# Power_Control.net
KiCad netlist of a schematic drawn in Altium Designer
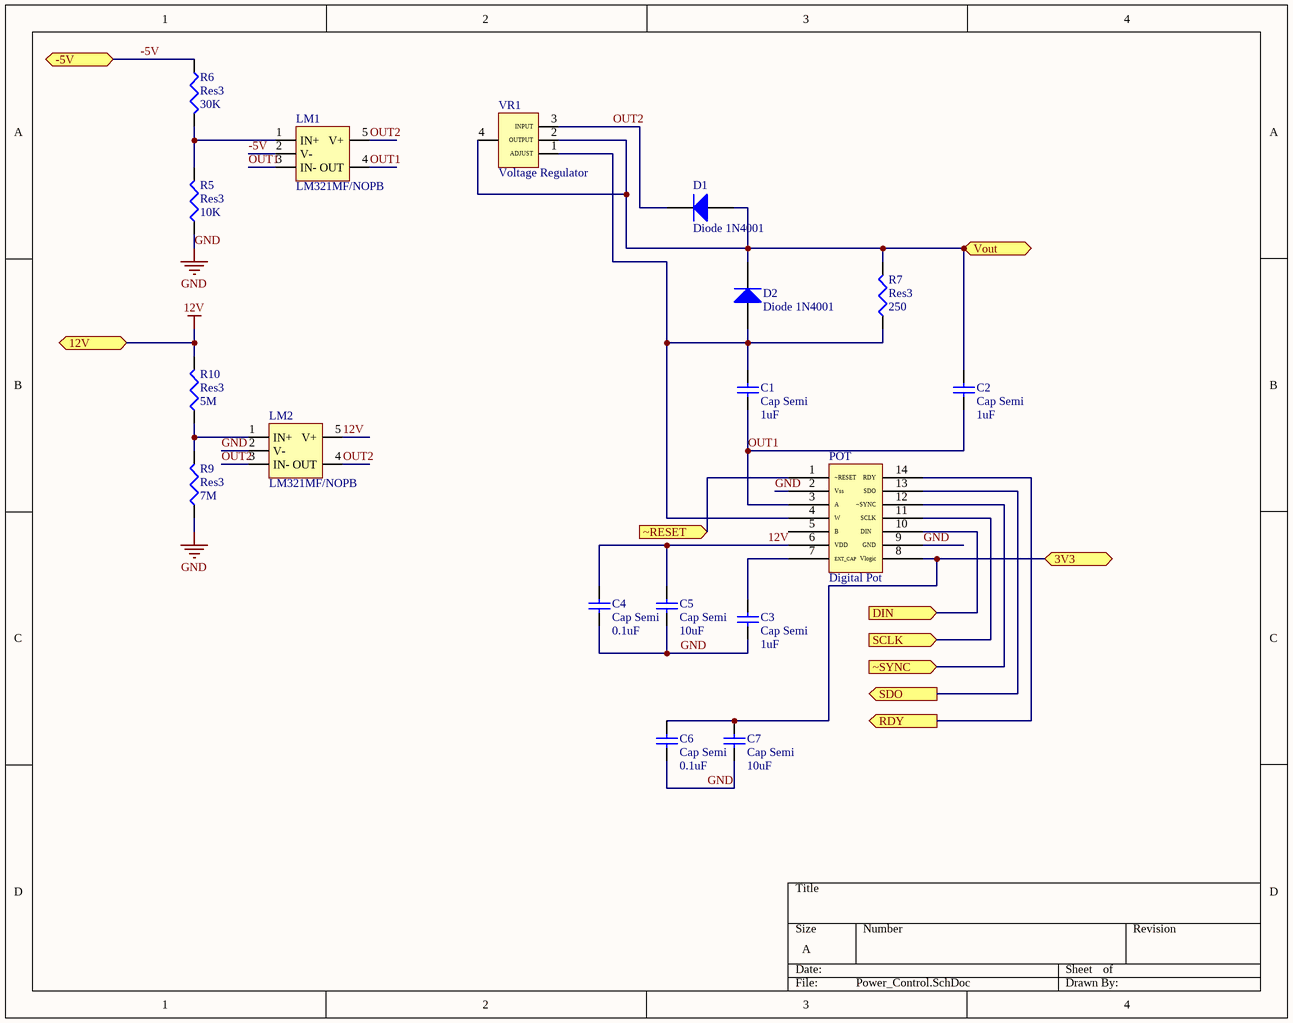
[diagram p0: Power_Control.SchDoc]

(export (version "E")
  (design (tool "Eeschema 10.0.6"))
  (components
    (comp (ref "C1")
      (value "Cap Semi")
      (footprint "C1206")
      (description "Capacitor (Semiconductor SIM Model)")
      (fields (field (name "ALTIUM_VALUE") "1uF") (field (name "PUBLISHER") "Altium Limited"))
      (libsource (lib "Miscellaneous Devices") (part "Cap Semi"))
    )
    (comp (ref "C2")
      (value "Cap Semi")
      (footprint "C1206")
      (description "Capacitor (Semiconductor SIM Model)")
      (fields (field (name "ALTIUM_VALUE") "1uF") (field (name "PUBLISHER") "Altium Limited"))
      (libsource (lib "Miscellaneous Devices") (part "Cap Semi"))
    )
    (comp (ref "C3")
      (value "Cap Semi")
      (footprint "C1206")
      (description "Capacitor (Semiconductor SIM Model)")
      (fields (field (name "ALTIUM_VALUE") "1uF") (field (name "PUBLISHER") "Altium Limited"))
      (libsource (lib "Miscellaneous Devices") (part "Cap Semi"))
    )
    (comp (ref "C4")
      (value "Cap Semi")
      (footprint "C1206")
      (description "Capacitor (Semiconductor SIM Model)")
      (fields (field (name "ALTIUM_VALUE") "0.1uF") (field (name "PUBLISHER") "Altium Limited"))
      (libsource (lib "Miscellaneous Devices") (part "Cap Semi"))
    )
    (comp (ref "C5")
      (value "Cap Semi")
      (footprint "C1206")
      (description "Capacitor (Semiconductor SIM Model)")
      (fields (field (name "ALTIUM_VALUE") "10uF") (field (name "PUBLISHER") "Altium Limited"))
      (libsource (lib "Miscellaneous Devices") (part "Cap Semi"))
    )
    (comp (ref "C6")
      (value "Cap Semi")
      (footprint "C1206")
      (description "Capacitor (Semiconductor SIM Model)")
      (fields (field (name "ALTIUM_VALUE") "0.1uF") (field (name "PUBLISHER") "Altium Limited"))
      (libsource (lib "Miscellaneous Devices") (part "Cap Semi"))
    )
    (comp (ref "C7")
      (value "Cap Semi")
      (footprint "C1206")
      (description "Capacitor (Semiconductor SIM Model)")
      (fields (field (name "ALTIUM_VALUE") "10uF") (field (name "PUBLISHER") "Altium Limited"))
      (libsource (lib "Miscellaneous Devices") (part "Cap Semi"))
    )
    (comp (ref "D1")
      (value "Diode 1N4001")
      (footprint "DO-41")
      (description "1 Amp General Purpose Rectifier")
      (fields (field (name "PUBLISHER") "Altium Limited"))
      (libsource (lib "Miscellaneous Devices") (part "Diode 1N4001"))
    )
    (comp (ref "D2")
      (value "Diode 1N4001")
      (footprint "DO-41")
      (description "1 Amp General Purpose Rectifier")
      (fields (field (name "PUBLISHER") "Altium Limited"))
      (libsource (lib "Miscellaneous Devices") (part "Diode 1N4001"))
    )
    (comp (ref "LM1")
      (value "LM321MF/NOPB")
      (description "IC OPAMP GP 1MHZ SOT23-5")
      (fields (field (name "MANUFACTURER") "Texas Instruments"))
      (libsource (lib "NORMS_LIB") (part "LM321MF/NOPB"))
    )
    (comp (ref "LM2")
      (value "LM321MF/NOPB")
      (description "IC OPAMP GP 1MHZ SOT23-5")
      (fields (field (name "MANUFACTURER") "Texas Instruments"))
      (libsource (lib "NORMS_LIB") (part "LM321MF/NOPB"))
    )
    (comp (ref "POT")
      (value "Digital Pot")
      (description "IC DGTL POT 1024POS 20K 14TSSOP")
      (fields
        (field (name "MANUFACTURER") "Analog Devices Inc.")
        (field (name "MANUFACTURER PART NUMBER") "AD5293BRUZ-20")
      )
      (libsource (lib "NORMS_LIB") (part "Digital Pot"))
    )
    (comp (ref "R5")
      (value "Res3")
      (footprint "J1-0603")
      (description "Resistor")
      (fields (field (name "ALTIUM_VALUE") "10K") (field (name "PUBLISHER") "Altium Limited"))
      (libsource (lib "Miscellaneous Devices") (part "Res3"))
    )
    (comp (ref "R6")
      (value "Res3")
      (footprint "J1-0603")
      (description "Resistor")
      (fields (field (name "ALTIUM_VALUE") "30K") (field (name "PUBLISHER") "Altium Limited"))
      (libsource (lib "Miscellaneous Devices") (part "Res3"))
    )
    (comp (ref "R7")
      (value "Res3")
      (footprint "J1-0603")
      (description "Resistor")
      (fields (field (name "ALTIUM_VALUE") "250") (field (name "PUBLISHER") "Altium Limited"))
      (libsource (lib "Miscellaneous Devices") (part "Res3"))
    )
    (comp (ref "R9")
      (value "Res3")
      (footprint "J1-0603")
      (description "Resistor")
      (fields (field (name "ALTIUM_VALUE") "7M") (field (name "PUBLISHER") "Altium Limited"))
      (libsource (lib "Miscellaneous Devices") (part "Res3"))
    )
    (comp (ref "R10")
      (value "Res3")
      (footprint "J1-0603")
      (description "Resistor")
      (fields (field (name "ALTIUM_VALUE") "5M") (field (name "PUBLISHER") "Altium Limited"))
      (libsource (lib "Miscellaneous Devices") (part "Res3"))
    )
    (comp (ref "VR1")
      (value "Voltage Regulator")
      (footprint "volt_reg")
      (description "IC REG LDO ADJ 1.5A DDPAK")
      (fields
        (field (name "MANUFACTURER") "Texas Instruments")
        (field (name "MANUFACTURER PART NUMBER") "LM317KTTR")
      )
      (libsource (lib "NORMS_LIB") (part "Voltage Regulator"))
    )
  )
  (nets
    (net (code "1") (name "/-5V") (class "Default")
      (node (ref "LM1") (pin "2") (pinfunction "V-_2") (pintype "passive"))
      (node (ref "R6") (pin "1") (pinfunction "1_1") (pintype "passive"))
    )
    (net (code "2") (name "/3V3") (class "Default")
      (node (ref "C6") (pin "2") (pinfunction "2_2") (pintype "passive"))
      (node (ref "C7") (pin "2") (pinfunction "2_2") (pintype "passive"))
      (node (ref "POT") (pin "8") (pinfunction "Vlogic_8") (pintype "passive"))
    )
    (net (code "3") (name "/DIN") (class "Default")
      (node (ref "POT") (pin "10") (pinfunction "DIN_10") (pintype "passive"))
    )
    (net (code "4") (name "/OUT1") (class "Default")
      (node (ref "C1") (pin "1") (pinfunction "1_1") (pintype "passive"))
      (node (ref "C2") (pin "1") (pinfunction "1_1") (pintype "passive"))
      (node (ref "LM1") (pin "3") (pinfunction "IN-_3") (pintype "passive"))
      (node (ref "LM1") (pin "4") (pinfunction "OUT_4") (pintype "passive"))
      (node (ref "POT") (pin "3") (pinfunction "A_3") (pintype "passive"))
    )
    (net (code "5") (name "/OUT2") (class "Default")
      (node (ref "D1") (pin "2") (pinfunction "K_2") (pintype "passive"))
      (node (ref "LM1") (pin "5") (pinfunction "V+_5") (pintype "passive"))
      (node (ref "LM2") (pin "3") (pinfunction "IN-_3") (pintype "passive"))
      (node (ref "LM2") (pin "4") (pinfunction "OUT_4") (pintype "passive"))
      (node (ref "VR1") (pin "3") (pinfunction "INPUT_3") (pintype "passive"))
    )
    (net (code "6") (name "/RDY") (class "Default")
      (node (ref "POT") (pin "14") (pinfunction "RDY_14") (pintype "passive"))
    )
    (net (code "7") (name "/SCLK") (class "Default")
      (node (ref "POT") (pin "11") (pinfunction "SCLK_11") (pintype "passive"))
    )
    (net (code "8") (name "/SDO") (class "Default")
      (node (ref "POT") (pin "13") (pinfunction "SDO_13") (pintype "passive"))
    )
    (net (code "9") (name "/Vout") (class "Default")
      (node (ref "C2") (pin "2") (pinfunction "2_2") (pintype "passive"))
      (node (ref "D1") (pin "1") (pinfunction "A_1") (pintype "passive"))
      (node (ref "D2") (pin "2") (pinfunction "K_2") (pintype "passive"))
      (node (ref "R7") (pin "2") (pinfunction "2_2") (pintype "passive"))
      (node (ref "VR1") (pin "2") (pinfunction "OUTPUT_2") (pintype "passive"))
      (node (ref "VR1") (pin "4") (pinfunction "Output_4") (pintype "passive"))
    )
    (net (code "10") (name "/~RESET") (class "Default")
      (node (ref "POT") (pin "1") (pinfunction "~RESET_1") (pintype "passive"))
    )
    (net (code "11") (name "/~SYNC") (class "Default")
      (node (ref "POT") (pin "12") (pinfunction "~SYNC_12") (pintype "passive"))
    )
    (net (code "12") (name "12V") (class "Default")
      (node (ref "C4") (pin "2") (pinfunction "2_2") (pintype "passive"))
      (node (ref "C5") (pin "2") (pinfunction "2_2") (pintype "passive"))
      (node (ref "LM2") (pin "5") (pinfunction "V+_5") (pintype "passive"))
      (node (ref "POT") (pin "6") (pinfunction "VDD_6") (pintype "passive"))
      (node (ref "R10") (pin "2") (pinfunction "2_2") (pintype "passive"))
    )
    (net (code "13") (name "GND") (class "Default")
      (node (ref "C3") (pin "1") (pinfunction "1_1") (pintype "passive"))
      (node (ref "C4") (pin "1") (pinfunction "1_1") (pintype "passive"))
      (node (ref "C5") (pin "1") (pinfunction "1_1") (pintype "passive"))
      (node (ref "C6") (pin "1") (pinfunction "1_1") (pintype "passive"))
      (node (ref "C7") (pin "1") (pinfunction "1_1") (pintype "passive"))
      (node (ref "LM2") (pin "2") (pinfunction "V-_2") (pintype "passive"))
      (node (ref "POT") (pin "2") (pinfunction "Vss_2") (pintype "passive"))
      (node (ref "POT") (pin "9") (pinfunction "GND_9") (pintype "passive"))
      (node (ref "R5") (pin "1") (pinfunction "1_1") (pintype "passive"))
      (node (ref "R9") (pin "1") (pinfunction "1_1") (pintype "passive"))
    )
    (net (code "14") (name "Net-(D2-A)") (class "Default")
      (node (ref "C1") (pin "2") (pinfunction "2_2") (pintype "passive"))
      (node (ref "D2") (pin "1") (pinfunction "A_1") (pintype "passive"))
      (node (ref "POT") (pin "4") (pinfunction "W_4") (pintype "passive"))
      (node (ref "R7") (pin "1") (pinfunction "1_1") (pintype "passive"))
      (node (ref "VR1") (pin "1") (pinfunction "ADJUST_1") (pintype "passive"))
    )
    (net (code "15") (name "Net-(LM1-IN+)") (class "Default")
      (node (ref "LM1") (pin "1") (pinfunction "IN+_1") (pintype "passive"))
      (node (ref "R5") (pin "2") (pinfunction "2_2") (pintype "passive"))
      (node (ref "R6") (pin "2") (pinfunction "2_2") (pintype "passive"))
    )
    (net (code "16") (name "Net-(LM2-IN+)") (class "Default")
      (node (ref "LM2") (pin "1") (pinfunction "IN+_1") (pintype "passive"))
      (node (ref "R10") (pin "1") (pinfunction "1_1") (pintype "passive"))
      (node (ref "R9") (pin "2") (pinfunction "2_2") (pintype "passive"))
    )
    (net (code "17") (name "Net-(POT-EXT_CAP)") (class "Default")
      (node (ref "C3") (pin "2") (pinfunction "2_2") (pintype "passive"))
      (node (ref "POT") (pin "7") (pinfunction "EXT_CAP_7") (pintype "passive"))
    )
    (net (code "18") (name "unconnected-(POT-B-Pad5)") (class "Default")
      (node (ref "POT") (pin "5") (pinfunction "B_5") (pintype "passive"))
    )
  )
)
